# mcu_v2.net
KiCad netlist of a schematic drawn in EAGLE
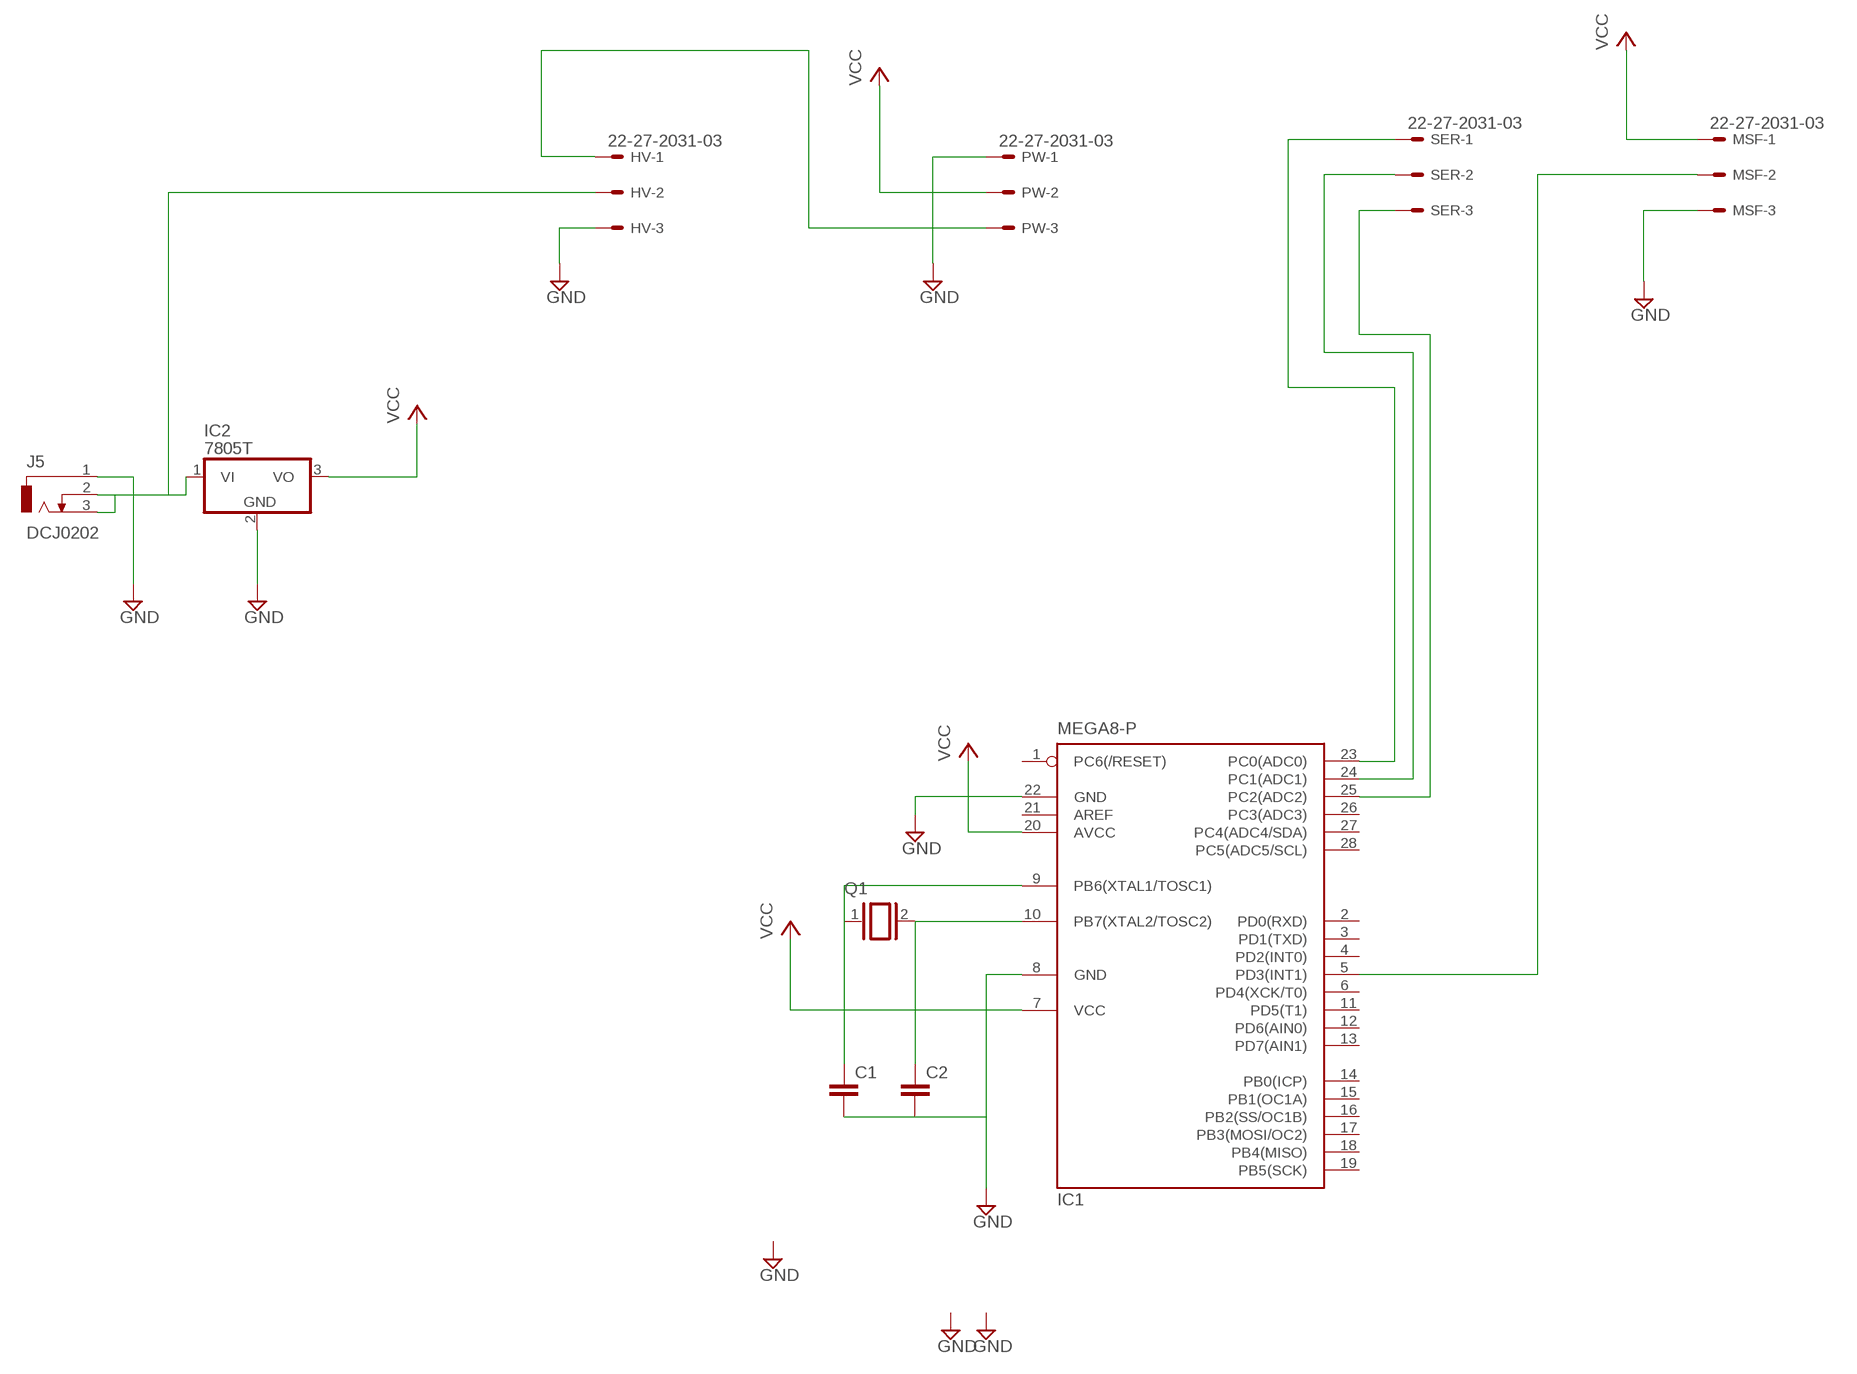
[diagram p0: schematic, sheet 1]

(export (version "E")
  (design (tool "Eeschema 10.0.6"))
  (components
    (comp (ref "C1")
      (value "C2,5-3")
      (footprint "eagle-import:C2.5-3")
      (libsource (lib "eagle-import") (part "C2,5-3"))
    )
    (comp (ref "C2")
      (value "C2,5-3")
      (footprint "eagle-import:C2.5-3")
      (libsource (lib "eagle-import") (part "C2,5-3"))
    )
    (comp (ref "HV")
      (value "22-27-2031-03")
      (footprint "eagle-import:6410-03")
      (libsource (lib "eagle-import") (part "22-?-0327-2031"))
    )
    (comp (ref "IC1")
      (value "MEGA8-P")
      (footprint "eagle-import:DIL28-3")
      (libsource (lib "eagle-import") (part "MEGA8-P"))
    )
    (comp (ref "IC2")
      (value "7805T")
      (footprint "eagle-import:TO220H")
      (libsource (lib "eagle-import") (part "78T05"))
    )
    (comp (ref "J5")
      (value "DCJ0202")
      (footprint "eagle-import:DCJ0202")
      (libsource (lib "eagle-import") (part "DCJ0202"))
    )
    (comp (ref "MSF")
      (value "22-27-2031-03")
      (footprint "eagle-import:6410-03")
      (libsource (lib "eagle-import") (part "22-?-0327-2031"))
    )
    (comp (ref "PW")
      (value "22-27-2031-03")
      (footprint "eagle-import:6410-03")
      (libsource (lib "eagle-import") (part "22-?-0327-2031"))
    )
    (comp (ref "Q1")
      (value "XTAL/S")
      (footprint "eagle-import:QS")
      (libsource (lib "eagle-import") (part "XTAL/S"))
    )
    (comp (ref "SER")
      (value "22-27-2031-03")
      (footprint "eagle-import:6410-03")
      (libsource (lib "eagle-import") (part "22-?-0327-2031"))
    )
  )
  (nets
    (net (code "1") (name "GND") (class "Default")
      (node (ref "C1") (pin "2") (pinfunction "2_2") (pintype "passive"))
      (node (ref "C2") (pin "2") (pinfunction "2_2") (pintype "passive"))
      (node (ref "HV") (pin "3") (pinfunction "S_3") (pintype "passive"))
      (node (ref "IC1") (pin "22") (pinfunction "GND_22") (pintype "power_in"))
      (node (ref "IC1") (pin "8") (pinfunction "GND_8") (pintype "power_in"))
      (node (ref "IC2") (pin "2") (pinfunction "GND_2") (pintype "passive"))
      (node (ref "J5") (pin "1") (pinfunction "1_1") (pintype "passive"))
      (node (ref "MSF") (pin "3") (pinfunction "S_3") (pintype "passive"))
      (node (ref "PW") (pin "1") (pinfunction "S_1") (pintype "passive"))
    )
    (net (code "2") (name "Net-(HVA-S)") (class "Default")
      (node (ref "HV") (pin "1") (pinfunction "S_1") (pintype "passive"))
      (node (ref "PW") (pin "3") (pinfunction "S_3") (pintype "passive"))
    )
    (net (code "3") (name "Net-(HVB-S)") (class "Default")
      (node (ref "HV") (pin "2") (pinfunction "S_2") (pintype "passive"))
      (node (ref "IC2") (pin "1") (pinfunction "VI_1") (pintype "input"))
      (node (ref "J5") (pin "2") (pinfunction "2_2") (pintype "passive"))
      (node (ref "J5") (pin "3") (pinfunction "3_3") (pintype "passive"))
    )
    (net (code "4") (name "Net-(IC1-PB6(XTAL1{slash}TOSC1))") (class "Default")
      (node (ref "C1") (pin "1") (pinfunction "1_1") (pintype "passive"))
      (node (ref "IC1") (pin "9") (pinfunction "PB6(XTAL1/TOSC1)_9") (pintype "bidirectional"))
      (node (ref "Q1") (pin "1") (pinfunction "1_1") (pintype "passive"))
    )
    (net (code "5") (name "Net-(IC1-PB7(XTAL2{slash}TOSC2))") (class "Default")
      (node (ref "C2") (pin "1") (pinfunction "1_1") (pintype "passive"))
      (node (ref "IC1") (pin "10") (pinfunction "PB7(XTAL2/TOSC2)_10") (pintype "bidirectional"))
      (node (ref "Q1") (pin "2") (pinfunction "2_2") (pintype "passive"))
    )
    (net (code "6") (name "Net-(IC1-PC0(ADC0))") (class "Default")
      (node (ref "IC1") (pin "23") (pinfunction "PC0(ADC0)_23") (pintype "bidirectional"))
      (node (ref "SER") (pin "1") (pinfunction "S_1") (pintype "passive"))
    )
    (net (code "7") (name "Net-(IC1-PC1(ADC1))") (class "Default")
      (node (ref "IC1") (pin "24") (pinfunction "PC1(ADC1)_24") (pintype "bidirectional"))
      (node (ref "SER") (pin "2") (pinfunction "S_2") (pintype "passive"))
    )
    (net (code "8") (name "Net-(IC1-PC2(ADC2))") (class "Default")
      (node (ref "IC1") (pin "25") (pinfunction "PC2(ADC2)_25") (pintype "bidirectional"))
      (node (ref "SER") (pin "3") (pinfunction "S_3") (pintype "passive"))
    )
    (net (code "9") (name "Net-(IC1-PD3(INT1))") (class "Default")
      (node (ref "IC1") (pin "5") (pinfunction "PD3(INT1)_5") (pintype "bidirectional"))
      (node (ref "MSF") (pin "2") (pinfunction "S_2") (pintype "passive"))
    )
    (net (code "10") (name "VCC") (class "Default")
      (node (ref "IC1") (pin "20") (pinfunction "AVCC_20") (pintype "power_in"))
      (node (ref "IC1") (pin "7") (pinfunction "VCC_7") (pintype "power_in"))
      (node (ref "IC2") (pin "3") (pinfunction "VO_3") (pintype "passive"))
      (node (ref "MSF") (pin "1") (pinfunction "S_1") (pintype "passive"))
      (node (ref "PW") (pin "2") (pinfunction "S_2") (pintype "passive"))
    )
    (net (code "11") (name "unconnected-(IC1-AREF-Pad21)") (class "Default")
      (node (ref "IC1") (pin "21") (pinfunction "AREF_21") (pintype "passive"))
    )
    (net (code "12") (name "unconnected-(IC1-PB0(ICP)-Pad14)") (class "Default")
      (node (ref "IC1") (pin "14") (pinfunction "PB0(ICP)_14") (pintype "bidirectional"))
    )
    (net (code "13") (name "unconnected-(IC1-PB1(OC1A)-Pad15)") (class "Default")
      (node (ref "IC1") (pin "15") (pinfunction "PB1(OC1A)_15") (pintype "bidirectional"))
    )
    (net (code "14") (name "unconnected-(IC1-PB2(SS{slash}OC1B)-Pad16)") (class "Default")
      (node (ref "IC1") (pin "16") (pinfunction "PB2(SS/OC1B)_16") (pintype "bidirectional"))
    )
    (net (code "15") (name "unconnected-(IC1-PB3(MOSI{slash}OC2)-Pad17)") (class "Default")
      (node (ref "IC1") (pin "17") (pinfunction "PB3(MOSI/OC2)_17") (pintype "bidirectional"))
    )
    (net (code "16") (name "unconnected-(IC1-PB4(MISO)-Pad18)") (class "Default")
      (node (ref "IC1") (pin "18") (pinfunction "PB4(MISO)_18") (pintype "bidirectional"))
    )
    (net (code "17") (name "unconnected-(IC1-PB5(SCK)-Pad19)") (class "Default")
      (node (ref "IC1") (pin "19") (pinfunction "PB5(SCK)_19") (pintype "bidirectional"))
    )
    (net (code "18") (name "unconnected-(IC1-PC3(ADC3)-Pad26)") (class "Default")
      (node (ref "IC1") (pin "26") (pinfunction "PC3(ADC3)_26") (pintype "bidirectional"))
    )
    (net (code "19") (name "unconnected-(IC1-PC4(ADC4{slash}SDA)-Pad27)") (class "Default")
      (node (ref "IC1") (pin "27") (pinfunction "PC4(ADC4/SDA)_27") (pintype "bidirectional"))
    )
    (net (code "20") (name "unconnected-(IC1-PC5(ADC5{slash}SCL)-Pad28)") (class "Default")
      (node (ref "IC1") (pin "28") (pinfunction "PC5(ADC5/SCL)_28") (pintype "bidirectional"))
    )
    (net (code "21") (name "unconnected-(IC1-PC6({slash}RESET)-Pad1)") (class "Default")
      (node (ref "IC1") (pin "1") (pinfunction "PC6(/RESET)_1") (pintype "bidirectional"))
    )
    (net (code "22") (name "unconnected-(IC1-PD0(RXD)-Pad2)") (class "Default")
      (node (ref "IC1") (pin "2") (pinfunction "PD0(RXD)_2") (pintype "bidirectional"))
    )
    (net (code "23") (name "unconnected-(IC1-PD1(TXD)-Pad3)") (class "Default")
      (node (ref "IC1") (pin "3") (pinfunction "PD1(TXD)_3") (pintype "bidirectional"))
    )
    (net (code "24") (name "unconnected-(IC1-PD2(INT0)-Pad4)") (class "Default")
      (node (ref "IC1") (pin "4") (pinfunction "PD2(INT0)_4") (pintype "bidirectional"))
    )
    (net (code "25") (name "unconnected-(IC1-PD4(XCK{slash}T0)-Pad6)") (class "Default")
      (node (ref "IC1") (pin "6") (pinfunction "PD4(XCK/T0)_6") (pintype "bidirectional"))
    )
    (net (code "26") (name "unconnected-(IC1-PD5(T1)-Pad11)") (class "Default")
      (node (ref "IC1") (pin "11") (pinfunction "PD5(T1)_11") (pintype "bidirectional"))
    )
    (net (code "27") (name "unconnected-(IC1-PD6(AIN0)-Pad12)") (class "Default")
      (node (ref "IC1") (pin "12") (pinfunction "PD6(AIN0)_12") (pintype "bidirectional"))
    )
    (net (code "28") (name "unconnected-(IC1-PD7(AIN1)-Pad13)") (class "Default")
      (node (ref "IC1") (pin "13") (pinfunction "PD7(AIN1)_13") (pintype "bidirectional"))
    )
  )
)
